# 09_-_CPU_GPIO.net
KiCad netlist of a schematic drawn in Altium Designer
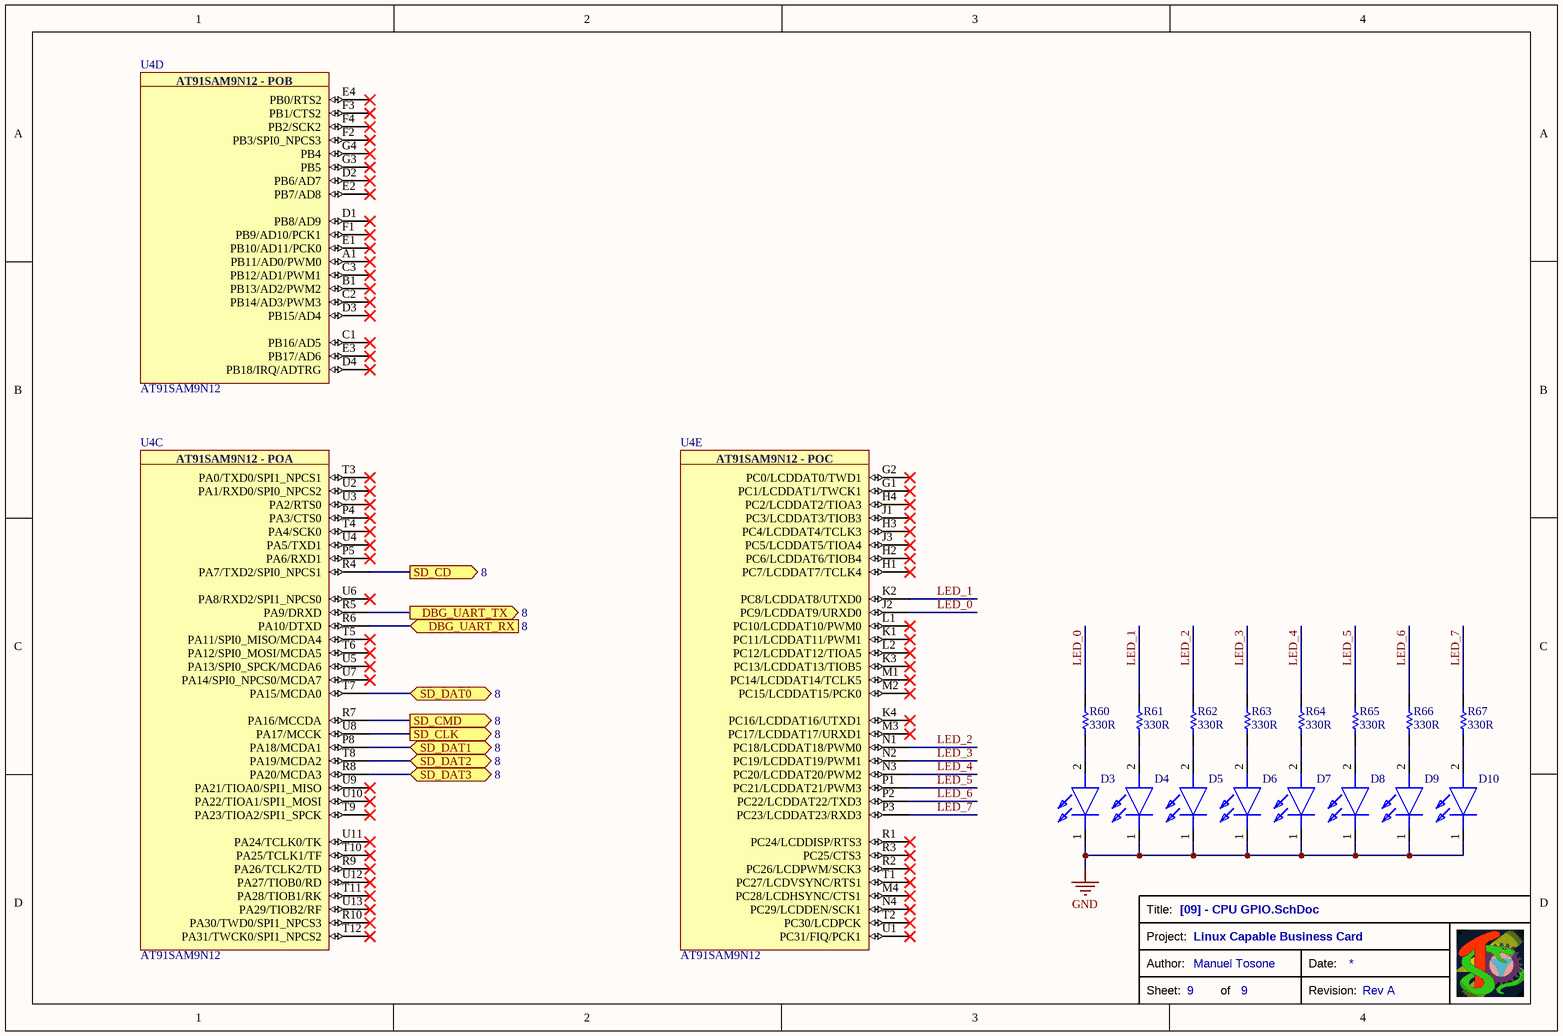
[diagram p0: [09] - CPU GPIO.SchDoc]

(export (version "E")
  (design (tool "Eeschema 10.0.6"))
  (components
    (comp (ref "D3")
      (value "150060VS75000")
      (footprint "LED-SMD-0603-1.6X0.8")
      (description "Standard LEDs - SMD WL-SMCW SMDMono TpVw Waterclr 0603 BrtGrn")
      (libsource (lib "Linux-Capable-Business-Card") (part "LED-SMD-0603-Green-150060VS75000"))
    )
    (comp (ref "D4")
      (value "150060VS75000")
      (footprint "LED-SMD-0603-1.6X0.8")
      (description "Standard LEDs - SMD WL-SMCW SMDMono TpVw Waterclr 0603 BrtGrn")
      (libsource (lib "Linux-Capable-Business-Card") (part "LED-SMD-0603-Green-150060VS75000"))
    )
    (comp (ref "D5")
      (value "150060VS75000")
      (footprint "LED-SMD-0603-1.6X0.8")
      (description "Standard LEDs - SMD WL-SMCW SMDMono TpVw Waterclr 0603 BrtGrn")
      (libsource (lib "Linux-Capable-Business-Card") (part "LED-SMD-0603-Green-150060VS75000"))
    )
    (comp (ref "D6")
      (value "150060VS75000")
      (footprint "LED-SMD-0603-1.6X0.8")
      (description "Standard LEDs - SMD WL-SMCW SMDMono TpVw Waterclr 0603 BrtGrn")
      (libsource (lib "Linux-Capable-Business-Card") (part "LED-SMD-0603-Green-150060VS75000"))
    )
    (comp (ref "D7")
      (value "150060VS75000")
      (footprint "LED-SMD-0603-1.6X0.8")
      (description "Standard LEDs - SMD WL-SMCW SMDMono TpVw Waterclr 0603 BrtGrn")
      (libsource (lib "Linux-Capable-Business-Card") (part "LED-SMD-0603-Green-150060VS75000"))
    )
    (comp (ref "D8")
      (value "150060VS75000")
      (footprint "LED-SMD-0603-1.6X0.8")
      (description "Standard LEDs - SMD WL-SMCW SMDMono TpVw Waterclr 0603 BrtGrn")
      (libsource (lib "Linux-Capable-Business-Card") (part "LED-SMD-0603-Green-150060VS75000"))
    )
    (comp (ref "D9")
      (value "150060VS75000")
      (footprint "LED-SMD-0603-1.6X0.8")
      (description "Standard LEDs - SMD WL-SMCW SMDMono TpVw Waterclr 0603 BrtGrn")
      (libsource (lib "Linux-Capable-Business-Card") (part "LED-SMD-0603-Green-150060VS75000"))
    )
    (comp (ref "D10")
      (value "150060VS75000")
      (footprint "LED-SMD-0603-1.6X0.8")
      (description "Standard LEDs - SMD WL-SMCW SMDMono TpVw Waterclr 0603 BrtGrn")
      (libsource (lib "Linux-Capable-Business-Card") (part "LED-SMD-0603-Green-150060VS75000"))
    )
    (comp (ref "R60")
      (value "330R")
      (footprint "RES-0603")
      (description "Thin Film Resistors - SMD 1/10W 330 ohm 1% 50ppm")
      (fields (field (name "MANUFACTURER") "Yageo") (field (name "Comment") "RT0603FRD07330RL"))
      (libsource (lib "Linux-Capable-Business-Card") (part "RES-0603-330R-RT0603FRD07330RL"))
    )
    (comp (ref "R61")
      (value "330R")
      (footprint "RES-0603")
      (description "Thin Film Resistors - SMD 1/10W 330 ohm 1% 50ppm")
      (fields (field (name "MANUFACTURER") "Yageo") (field (name "Comment") "RT0603FRD07330RL"))
      (libsource (lib "Linux-Capable-Business-Card") (part "RES-0603-330R-RT0603FRD07330RL"))
    )
    (comp (ref "R62")
      (value "330R")
      (footprint "RES-0603")
      (description "Thin Film Resistors - SMD 1/10W 330 ohm 1% 50ppm")
      (fields (field (name "MANUFACTURER") "Yageo") (field (name "Comment") "RT0603FRD07330RL"))
      (libsource (lib "Linux-Capable-Business-Card") (part "RES-0603-330R-RT0603FRD07330RL"))
    )
    (comp (ref "R63")
      (value "330R")
      (footprint "RES-0603")
      (description "Thin Film Resistors - SMD 1/10W 330 ohm 1% 50ppm")
      (fields (field (name "MANUFACTURER") "Yageo") (field (name "Comment") "RT0603FRD07330RL"))
      (libsource (lib "Linux-Capable-Business-Card") (part "RES-0603-330R-RT0603FRD07330RL"))
    )
    (comp (ref "R64")
      (value "330R")
      (footprint "RES-0603")
      (description "Thin Film Resistors - SMD 1/10W 330 ohm 1% 50ppm")
      (fields (field (name "MANUFACTURER") "Yageo") (field (name "Comment") "RT0603FRD07330RL"))
      (libsource (lib "Linux-Capable-Business-Card") (part "RES-0603-330R-RT0603FRD07330RL"))
    )
    (comp (ref "R65")
      (value "330R")
      (footprint "RES-0603")
      (description "Thin Film Resistors - SMD 1/10W 330 ohm 1% 50ppm")
      (fields (field (name "MANUFACTURER") "Yageo") (field (name "Comment") "RT0603FRD07330RL"))
      (libsource (lib "Linux-Capable-Business-Card") (part "RES-0603-330R-RT0603FRD07330RL"))
    )
    (comp (ref "R66")
      (value "330R")
      (footprint "RES-0603")
      (description "Thin Film Resistors - SMD 1/10W 330 ohm 1% 50ppm")
      (fields (field (name "MANUFACTURER") "Yageo") (field (name "Comment") "RT0603FRD07330RL"))
      (libsource (lib "Linux-Capable-Business-Card") (part "RES-0603-330R-RT0603FRD07330RL"))
    )
    (comp (ref "R67")
      (value "330R")
      (footprint "RES-0603")
      (description "Thin Film Resistors - SMD 1/10W 330 ohm 1% 50ppm")
      (fields (field (name "MANUFACTURER") "Yageo") (field (name "Comment") "RT0603FRD07330RL"))
      (libsource (lib "Linux-Capable-Business-Card") (part "RES-0603-330R-RT0603FRD07330RL"))
    )
    (comp (ref "U4")
      (value "AT91SAM9N12")
      (footprint "BGA0.8P17X17_217_15X15")
      (description "MPU ARM926EJ-S 400MHz")
      (libsource (lib "Linux-Capable-Business-Card") (part "AT91SAM9N12"))
    )
  )
  (nets
    (net (code "1") (name "/DBG_UART_RX") (class "Default")
      (node (ref "U4") (pin "R6") (pinfunction "PA10/DTXD_R6") (pintype "bidirectional"))
    )
    (net (code "2") (name "/DBG_UART_TX") (class "Default")
      (node (ref "U4") (pin "R5") (pinfunction "PA9/DRXD_R5") (pintype "bidirectional"))
    )
    (net (code "3") (name "/LED_0") (class "Default")
      (node (ref "R60") (pin "2") (pinfunction "2_2") (pintype "passive"))
      (node (ref "U4") (pin "J2") (pinfunction "PC9/LCDDAT9/URXD0_J2") (pintype "bidirectional"))
    )
    (net (code "4") (name "/LED_1") (class "Default")
      (node (ref "R61") (pin "2") (pinfunction "2_2") (pintype "passive"))
      (node (ref "U4") (pin "K2") (pinfunction "PC8/LCDDAT8/UTXD0_K2") (pintype "bidirectional"))
    )
    (net (code "5") (name "/LED_2") (class "Default")
      (node (ref "R62") (pin "2") (pinfunction "2_2") (pintype "passive"))
      (node (ref "U4") (pin "N1") (pinfunction "PC18/LCDDAT18/PWM0_N1") (pintype "bidirectional"))
    )
    (net (code "6") (name "/LED_3") (class "Default")
      (node (ref "R63") (pin "2") (pinfunction "2_2") (pintype "passive"))
      (node (ref "U4") (pin "N2") (pinfunction "PC19/LCDDAT19/PWM1_N2") (pintype "bidirectional"))
    )
    (net (code "7") (name "/LED_4") (class "Default")
      (node (ref "R64") (pin "2") (pinfunction "2_2") (pintype "passive"))
      (node (ref "U4") (pin "N3") (pinfunction "PC20/LCDDAT20/PWM2_N3") (pintype "bidirectional"))
    )
    (net (code "8") (name "/LED_5") (class "Default")
      (node (ref "R65") (pin "2") (pinfunction "2_2") (pintype "passive"))
      (node (ref "U4") (pin "P1") (pinfunction "PC21/LCDDAT21/PWM3_P1") (pintype "bidirectional"))
    )
    (net (code "9") (name "/LED_6") (class "Default")
      (node (ref "R66") (pin "2") (pinfunction "2_2") (pintype "passive"))
      (node (ref "U4") (pin "P2") (pinfunction "PC22/LCDDAT22/TXD3_P2") (pintype "bidirectional"))
    )
    (net (code "10") (name "/LED_7") (class "Default")
      (node (ref "R67") (pin "2") (pinfunction "2_2") (pintype "passive"))
      (node (ref "U4") (pin "P3") (pinfunction "PC23/LCDDAT23/RXD3_P3") (pintype "bidirectional"))
    )
    (net (code "11") (name "/SD_CD") (class "Default")
      (node (ref "U4") (pin "R4") (pinfunction "PA7/TXD2/SPI0_NPCS1_R4") (pintype "bidirectional"))
    )
    (net (code "12") (name "/SD_CLK") (class "Default")
      (node (ref "U4") (pin "U8") (pinfunction "PA17/MCCK_U8") (pintype "bidirectional"))
    )
    (net (code "13") (name "/SD_CMD") (class "Default")
      (node (ref "U4") (pin "R7") (pinfunction "PA16/MCCDA_R7") (pintype "bidirectional"))
    )
    (net (code "14") (name "/SD_DAT0") (class "Default")
      (node (ref "U4") (pin "T7") (pinfunction "PA15/MCDA0_T7") (pintype "bidirectional"))
    )
    (net (code "15") (name "/SD_DAT1") (class "Default")
      (node (ref "U4") (pin "P8") (pinfunction "PA18/MCDA1_P8") (pintype "bidirectional"))
    )
    (net (code "16") (name "/SD_DAT2") (class "Default")
      (node (ref "U4") (pin "T8") (pinfunction "PA19/MCDA2_T8") (pintype "bidirectional"))
    )
    (net (code "17") (name "/SD_DAT3") (class "Default")
      (node (ref "U4") (pin "R8") (pinfunction "PA20/MCDA3_R8") (pintype "bidirectional"))
    )
    (net (code "18") (name "GND") (class "Default")
      (node (ref "D10") (pin "1") (pinfunction "K_1") (pintype "passive"))
      (node (ref "D3") (pin "1") (pinfunction "K_1") (pintype "passive"))
      (node (ref "D4") (pin "1") (pinfunction "K_1") (pintype "passive"))
      (node (ref "D5") (pin "1") (pinfunction "K_1") (pintype "passive"))
      (node (ref "D6") (pin "1") (pinfunction "K_1") (pintype "passive"))
      (node (ref "D7") (pin "1") (pinfunction "K_1") (pintype "passive"))
      (node (ref "D8") (pin "1") (pinfunction "K_1") (pintype "passive"))
      (node (ref "D9") (pin "1") (pinfunction "K_1") (pintype "passive"))
    )
    (net (code "19") (name "Net-(D3-A)") (class "Default")
      (node (ref "D3") (pin "2") (pinfunction "A_2") (pintype "passive"))
      (node (ref "R60") (pin "1") (pinfunction "1_1") (pintype "passive"))
    )
    (net (code "20") (name "Net-(D4-A)") (class "Default")
      (node (ref "D4") (pin "2") (pinfunction "A_2") (pintype "passive"))
      (node (ref "R61") (pin "1") (pinfunction "1_1") (pintype "passive"))
    )
    (net (code "21") (name "Net-(D5-A)") (class "Default")
      (node (ref "D5") (pin "2") (pinfunction "A_2") (pintype "passive"))
      (node (ref "R62") (pin "1") (pinfunction "1_1") (pintype "passive"))
    )
    (net (code "22") (name "Net-(D6-A)") (class "Default")
      (node (ref "D6") (pin "2") (pinfunction "A_2") (pintype "passive"))
      (node (ref "R63") (pin "1") (pinfunction "1_1") (pintype "passive"))
    )
    (net (code "23") (name "Net-(D7-A)") (class "Default")
      (node (ref "D7") (pin "2") (pinfunction "A_2") (pintype "passive"))
      (node (ref "R64") (pin "1") (pinfunction "1_1") (pintype "passive"))
    )
    (net (code "24") (name "Net-(D8-A)") (class "Default")
      (node (ref "D8") (pin "2") (pinfunction "A_2") (pintype "passive"))
      (node (ref "R65") (pin "1") (pinfunction "1_1") (pintype "passive"))
    )
    (net (code "25") (name "Net-(D9-A)") (class "Default")
      (node (ref "D9") (pin "2") (pinfunction "A_2") (pintype "passive"))
      (node (ref "R66") (pin "1") (pinfunction "1_1") (pintype "passive"))
    )
    (net (code "26") (name "Net-(D10-A)") (class "Default")
      (node (ref "D10") (pin "2") (pinfunction "A_2") (pintype "passive"))
      (node (ref "R67") (pin "1") (pinfunction "1_1") (pintype "passive"))
    )
    (net (code "27") (name "unconnected-(U4C-PA0{slash}TXD0{slash}SPI1_NPCS1-PadT3)") (class "Default")
      (node (ref "U4") (pin "T3") (pinfunction "PA0/TXD0/SPI1_NPCS1_T3") (pintype "bidirectional+no_connect"))
    )
    (net (code "28") (name "unconnected-(U4C-PA1{slash}RXD0{slash}SPI0_NPCS2-PadU2)") (class "Default")
      (node (ref "U4") (pin "U2") (pinfunction "PA1/RXD0/SPI0_NPCS2_U2") (pintype "bidirectional+no_connect"))
    )
    (net (code "29") (name "unconnected-(U4C-PA2{slash}RTS0-PadU3)") (class "Default")
      (node (ref "U4") (pin "U3") (pinfunction "PA2/RTS0_U3") (pintype "bidirectional+no_connect"))
    )
    (net (code "30") (name "unconnected-(U4C-PA3{slash}CTS0-PadP4)") (class "Default")
      (node (ref "U4") (pin "P4") (pinfunction "PA3/CTS0_P4") (pintype "bidirectional+no_connect"))
    )
    (net (code "31") (name "unconnected-(U4C-PA4{slash}SCK0-PadT4)") (class "Default")
      (node (ref "U4") (pin "T4") (pinfunction "PA4/SCK0_T4") (pintype "bidirectional+no_connect"))
    )
    (net (code "32") (name "unconnected-(U4C-PA5{slash}TXD1-PadU4)") (class "Default")
      (node (ref "U4") (pin "U4") (pinfunction "PA5/TXD1_U4") (pintype "bidirectional+no_connect"))
    )
    (net (code "33") (name "unconnected-(U4C-PA6{slash}RXD1-PadP5)") (class "Default")
      (node (ref "U4") (pin "P5") (pinfunction "PA6/RXD1_P5") (pintype "bidirectional+no_connect"))
    )
    (net (code "34") (name "unconnected-(U4C-PA8{slash}RXD2{slash}SPI1_NPCS0-PadU6)") (class "Default")
      (node (ref "U4") (pin "U6") (pinfunction "PA8/RXD2/SPI1_NPCS0_U6") (pintype "bidirectional+no_connect"))
    )
    (net (code "35") (name "unconnected-(U4C-PA11{slash}SPI0_MISO{slash}MCDA4-PadT5)") (class "Default")
      (node (ref "U4") (pin "T5") (pinfunction "PA11/SPI0_MISO/MCDA4_T5") (pintype "bidirectional+no_connect"))
    )
    (net (code "36") (name "unconnected-(U4C-PA12{slash}SPI0_MOSI{slash}MCDA5-PadT6)") (class "Default")
      (node (ref "U4") (pin "T6") (pinfunction "PA12/SPI0_MOSI/MCDA5_T6") (pintype "bidirectional+no_connect"))
    )
    (net (code "37") (name "unconnected-(U4C-PA13{slash}SPI0_SPCK{slash}MCDA6-PadU5)") (class "Default")
      (node (ref "U4") (pin "U5") (pinfunction "PA13/SPI0_SPCK/MCDA6_U5") (pintype "bidirectional+no_connect"))
    )
    (net (code "38") (name "unconnected-(U4C-PA14{slash}SPI0_NPCS0{slash}MCDA7-PadU7)") (class "Default")
      (node (ref "U4") (pin "U7") (pinfunction "PA14/SPI0_NPCS0/MCDA7_U7") (pintype "bidirectional+no_connect"))
    )
    (net (code "39") (name "unconnected-(U4C-PA21{slash}TIOA0{slash}SPI1_MISO-PadU9)") (class "Default")
      (node (ref "U4") (pin "U9") (pinfunction "PA21/TIOA0/SPI1_MISO_U9") (pintype "bidirectional+no_connect"))
    )
    (net (code "40") (name "unconnected-(U4C-PA22{slash}TIOA1{slash}SPI1_MOSI-PadU10)") (class "Default")
      (node (ref "U4") (pin "U10") (pinfunction "PA22/TIOA1/SPI1_MOSI_U10") (pintype "bidirectional+no_connect"))
    )
    (net (code "41") (name "unconnected-(U4C-PA23{slash}TIOA2{slash}SPI1_SPCK-PadT9)") (class "Default")
      (node (ref "U4") (pin "T9") (pinfunction "PA23/TIOA2/SPI1_SPCK_T9") (pintype "bidirectional+no_connect"))
    )
    (net (code "42") (name "unconnected-(U4C-PA24{slash}TCLK0{slash}TK-PadU11)") (class "Default")
      (node (ref "U4") (pin "U11") (pinfunction "PA24/TCLK0/TK_U11") (pintype "bidirectional+no_connect"))
    )
    (net (code "43") (name "unconnected-(U4C-PA25{slash}TCLK1{slash}TF-PadT10)") (class "Default")
      (node (ref "U4") (pin "T10") (pinfunction "PA25/TCLK1/TF_T10") (pintype "bidirectional+no_connect"))
    )
    (net (code "44") (name "unconnected-(U4C-PA26{slash}TCLK2{slash}TD-PadR9)") (class "Default")
      (node (ref "U4") (pin "R9") (pinfunction "PA26/TCLK2/TD_R9") (pintype "bidirectional+no_connect"))
    )
    (net (code "45") (name "unconnected-(U4C-PA27{slash}TIOB0{slash}RD-PadU12)") (class "Default")
      (node (ref "U4") (pin "U12") (pinfunction "PA27/TIOB0/RD_U12") (pintype "bidirectional+no_connect"))
    )
    (net (code "46") (name "unconnected-(U4C-PA28{slash}TIOB1{slash}RK-PadT11)") (class "Default")
      (node (ref "U4") (pin "T11") (pinfunction "PA28/TIOB1/RK_T11") (pintype "bidirectional+no_connect"))
    )
    (net (code "47") (name "unconnected-(U4C-PA29{slash}TIOB2{slash}RF-PadU13)") (class "Default")
      (node (ref "U4") (pin "U13") (pinfunction "PA29/TIOB2/RF_U13") (pintype "bidirectional+no_connect"))
    )
    (net (code "48") (name "unconnected-(U4C-PA30{slash}TWD0{slash}SPI1_NPCS3-PadR10)") (class "Default")
      (node (ref "U4") (pin "R10") (pinfunction "PA30/TWD0/SPI1_NPCS3_R10") (pintype "bidirectional+no_connect"))
    )
    (net (code "49") (name "unconnected-(U4C-PA31{slash}TWCK0{slash}SPI1_NPCS2-PadT12)") (class "Default")
      (node (ref "U4") (pin "T12") (pinfunction "PA31/TWCK0/SPI1_NPCS2_T12") (pintype "bidirectional+no_connect"))
    )
    (net (code "50") (name "unconnected-(U4D-PB0{slash}RTS2-PadE4)") (class "Default")
      (node (ref "U4") (pin "E4") (pinfunction "PB0/RTS2_E4") (pintype "bidirectional+no_connect"))
    )
    (net (code "51") (name "unconnected-(U4D-PB1{slash}CTS2-PadF3)") (class "Default")
      (node (ref "U4") (pin "F3") (pinfunction "PB1/CTS2_F3") (pintype "bidirectional+no_connect"))
    )
    (net (code "52") (name "unconnected-(U4D-PB2{slash}SCK2-PadF4)") (class "Default")
      (node (ref "U4") (pin "F4") (pinfunction "PB2/SCK2_F4") (pintype "bidirectional+no_connect"))
    )
    (net (code "53") (name "unconnected-(U4D-PB3{slash}SPI0_NPCS3-PadF2)") (class "Default")
      (node (ref "U4") (pin "F2") (pinfunction "PB3/SPI0_NPCS3_F2") (pintype "bidirectional+no_connect"))
    )
    (net (code "54") (name "unconnected-(U4D-PB4-PadG4)") (class "Default")
      (node (ref "U4") (pin "G4") (pinfunction "PB4_G4") (pintype "bidirectional+no_connect"))
    )
    (net (code "55") (name "unconnected-(U4D-PB5-PadG3)") (class "Default")
      (node (ref "U4") (pin "G3") (pinfunction "PB5_G3") (pintype "bidirectional+no_connect"))
    )
    (net (code "56") (name "unconnected-(U4D-PB6{slash}AD7-PadD2)") (class "Default")
      (node (ref "U4") (pin "D2") (pinfunction "PB6/AD7_D2") (pintype "bidirectional+no_connect"))
    )
    (net (code "57") (name "unconnected-(U4D-PB7{slash}AD8-PadE2)") (class "Default")
      (node (ref "U4") (pin "E2") (pinfunction "PB7/AD8_E2") (pintype "bidirectional+no_connect"))
    )
    (net (code "58") (name "unconnected-(U4D-PB8{slash}AD9-PadD1)") (class "Default")
      (node (ref "U4") (pin "D1") (pinfunction "PB8/AD9_D1") (pintype "bidirectional+no_connect"))
    )
    (net (code "59") (name "unconnected-(U4D-PB9{slash}AD10{slash}PCK1-PadF1)") (class "Default")
      (node (ref "U4") (pin "F1") (pinfunction "PB9/AD10/PCK1_F1") (pintype "bidirectional+no_connect"))
    )
    (net (code "60") (name "unconnected-(U4D-PB10{slash}AD11{slash}PCK0-PadE1)") (class "Default")
      (node (ref "U4") (pin "E1") (pinfunction "PB10/AD11/PCK0_E1") (pintype "bidirectional+no_connect"))
    )
    (net (code "61") (name "unconnected-(U4D-PB11{slash}AD0{slash}PWM0-PadA1)") (class "Default")
      (node (ref "U4") (pin "A1") (pinfunction "PB11/AD0/PWM0_A1") (pintype "bidirectional+no_connect"))
    )
    (net (code "62") (name "unconnected-(U4D-PB12{slash}AD1{slash}PWM1-PadC3)") (class "Default")
      (node (ref "U4") (pin "C3") (pinfunction "PB12/AD1/PWM1_C3") (pintype "bidirectional+no_connect"))
    )
    (net (code "63") (name "unconnected-(U4D-PB13{slash}AD2{slash}PWM2-PadB1)") (class "Default")
      (node (ref "U4") (pin "B1") (pinfunction "PB13/AD2/PWM2_B1") (pintype "bidirectional+no_connect"))
    )
    (net (code "64") (name "unconnected-(U4D-PB14{slash}AD3{slash}PWM3-PadC2)") (class "Default")
      (node (ref "U4") (pin "C2") (pinfunction "PB14/AD3/PWM3_C2") (pintype "bidirectional+no_connect"))
    )
    (net (code "65") (name "unconnected-(U4D-PB15{slash}AD4-PadD3)") (class "Default")
      (node (ref "U4") (pin "D3") (pinfunction "PB15/AD4_D3") (pintype "bidirectional+no_connect"))
    )
    (net (code "66") (name "unconnected-(U4D-PB16{slash}AD5-PadC1)") (class "Default")
      (node (ref "U4") (pin "C1") (pinfunction "PB16/AD5_C1") (pintype "bidirectional+no_connect"))
    )
    (net (code "67") (name "unconnected-(U4D-PB17{slash}AD6-PadE3)") (class "Default")
      (node (ref "U4") (pin "E3") (pinfunction "PB17/AD6_E3") (pintype "bidirectional+no_connect"))
    )
    (net (code "68") (name "unconnected-(U4D-PB18{slash}IRQ{slash}ADTRG-PadD4)") (class "Default")
      (node (ref "U4") (pin "D4") (pinfunction "PB18/IRQ/ADTRG_D4") (pintype "bidirectional+no_connect"))
    )
    (net (code "69") (name "unconnected-(U4E-PC0{slash}LCDDAT0{slash}TWD1-PadG2)") (class "Default")
      (node (ref "U4") (pin "G2") (pinfunction "PC0/LCDDAT0/TWD1_G2") (pintype "bidirectional+no_connect"))
    )
    (net (code "70") (name "unconnected-(U4E-PC1{slash}LCDDAT1{slash}TWCK1-PadG1)") (class "Default")
      (node (ref "U4") (pin "G1") (pinfunction "PC1/LCDDAT1/TWCK1_G1") (pintype "bidirectional+no_connect"))
    )
    (net (code "71") (name "unconnected-(U4E-PC2{slash}LCDDAT2{slash}TIOA3-PadH4)") (class "Default")
      (node (ref "U4") (pin "H4") (pinfunction "PC2/LCDDAT2/TIOA3_H4") (pintype "bidirectional+no_connect"))
    )
    (net (code "72") (name "unconnected-(U4E-PC3{slash}LCDDAT3{slash}TIOB3-PadJ1)") (class "Default")
      (node (ref "U4") (pin "J1") (pinfunction "PC3/LCDDAT3/TIOB3_J1") (pintype "bidirectional+no_connect"))
    )
    (net (code "73") (name "unconnected-(U4E-PC4{slash}LCDDAT4{slash}TCLK3-PadH3)") (class "Default")
      (node (ref "U4") (pin "H3") (pinfunction "PC4/LCDDAT4/TCLK3_H3") (pintype "bidirectional+no_connect"))
    )
    (net (code "74") (name "unconnected-(U4E-PC5{slash}LCDDAT5{slash}TIOA4-PadJ3)") (class "Default")
      (node (ref "U4") (pin "J3") (pinfunction "PC5/LCDDAT5/TIOA4_J3") (pintype "bidirectional+no_connect"))
    )
    (net (code "75") (name "unconnected-(U4E-PC6{slash}LCDDAT6{slash}TIOB4-PadH2)") (class "Default")
      (node (ref "U4") (pin "H2") (pinfunction "PC6/LCDDAT6/TIOB4_H2") (pintype "bidirectional+no_connect"))
    )
    (net (code "76") (name "unconnected-(U4E-PC7{slash}LCDDAT7{slash}TCLK4-PadH1)") (class "Default")
      (node (ref "U4") (pin "H1") (pinfunction "PC7/LCDDAT7/TCLK4_H1") (pintype "bidirectional+no_connect"))
    )
    (net (code "77") (name "unconnected-(U4E-PC10{slash}LCDDAT10{slash}PWM0-PadL1)") (class "Default")
      (node (ref "U4") (pin "L1") (pinfunction "PC10/LCDDAT10/PWM0_L1") (pintype "bidirectional+no_connect"))
    )
    (net (code "78") (name "unconnected-(U4E-PC11{slash}LCDDAT11{slash}PWM1-PadK1)") (class "Default")
      (node (ref "U4") (pin "K1") (pinfunction "PC11/LCDDAT11/PWM1_K1") (pintype "bidirectional+no_connect"))
    )
    (net (code "79") (name "unconnected-(U4E-PC12{slash}LCDDAT12{slash}TIOA5-PadL2)") (class "Default")
      (node (ref "U4") (pin "L2") (pinfunction "PC12/LCDDAT12/TIOA5_L2") (pintype "bidirectional+no_connect"))
    )
    (net (code "80") (name "unconnected-(U4E-PC13{slash}LCDDAT13{slash}TIOB5-PadK3)") (class "Default")
      (node (ref "U4") (pin "K3") (pinfunction "PC13/LCDDAT13/TIOB5_K3") (pintype "bidirectional+no_connect"))
    )
    (net (code "81") (name "unconnected-(U4E-PC14{slash}LCDDAT14{slash}TCLK5-PadM1)") (class "Default")
      (node (ref "U4") (pin "M1") (pinfunction "PC14/LCDDAT14/TCLK5_M1") (pintype "bidirectional+no_connect"))
    )
    (net (code "82") (name "unconnected-(U4E-PC15{slash}LCDDAT15{slash}PCK0-PadM2)") (class "Default")
      (node (ref "U4") (pin "M2") (pinfunction "PC15/LCDDAT15/PCK0_M2") (pintype "bidirectional+no_connect"))
    )
    (net (code "83") (name "unconnected-(U4E-PC16{slash}LCDDAT16{slash}UTXD1-PadK4)") (class "Default")
      (node (ref "U4") (pin "K4") (pinfunction "PC16/LCDDAT16/UTXD1_K4") (pintype "bidirectional+no_connect"))
    )
    (net (code "84") (name "unconnected-(U4E-PC17{slash}LCDDAT17{slash}URXD1-PadM3)") (class "Default")
      (node (ref "U4") (pin "M3") (pinfunction "PC17/LCDDAT17/URXD1_M3") (pintype "bidirectional+no_connect"))
    )
    (net (code "85") (name "unconnected-(U4E-PC24{slash}LCDDISP{slash}RTS3-PadR1)") (class "Default")
      (node (ref "U4") (pin "R1") (pinfunction "PC24/LCDDISP/RTS3_R1") (pintype "bidirectional+no_connect"))
    )
    (net (code "86") (name "unconnected-(U4E-PC25{slash}CTS3-PadR3)") (class "Default")
      (node (ref "U4") (pin "R3") (pinfunction "PC25/CTS3_R3") (pintype "bidirectional+no_connect"))
    )
    (net (code "87") (name "unconnected-(U4E-PC26{slash}LCDPWM{slash}SCK3-PadR2)") (class "Default")
      (node (ref "U4") (pin "R2") (pinfunction "PC26/LCDPWM/SCK3_R2") (pintype "bidirectional+no_connect"))
    )
    (net (code "88") (name "unconnected-(U4E-PC27{slash}LCDVSYNC{slash}RTS1-PadT1)") (class "Default")
      (node (ref "U4") (pin "T1") (pinfunction "PC27/LCDVSYNC/RTS1_T1") (pintype "bidirectional+no_connect"))
    )
    (net (code "89") (name "unconnected-(U4E-PC28{slash}LCDHSYNC{slash}CTS1-PadM4)") (class "Default")
      (node (ref "U4") (pin "M4") (pinfunction "PC28/LCDHSYNC/CTS1_M4") (pintype "bidirectional+no_connect"))
    )
    (net (code "90") (name "unconnected-(U4E-PC29{slash}LCDDEN{slash}SCK1-PadN4)") (class "Default")
      (node (ref "U4") (pin "N4") (pinfunction "PC29/LCDDEN/SCK1_N4") (pintype "bidirectional+no_connect"))
    )
    (net (code "91") (name "unconnected-(U4E-PC30{slash}LCDPCK-PadT2)") (class "Default")
      (node (ref "U4") (pin "T2") (pinfunction "PC30/LCDPCK_T2") (pintype "bidirectional+no_connect"))
    )
    (net (code "92") (name "unconnected-(U4E-PC31{slash}FIQ{slash}PCK1-PadU1)") (class "Default")
      (node (ref "U4") (pin "U1") (pinfunction "PC31/FIQ/PCK1_U1") (pintype "bidirectional+no_connect"))
    )
  )
)
